# BAAAHS-BRN01-E.net
KiCad netlist of a schematic drawn in EAGLE
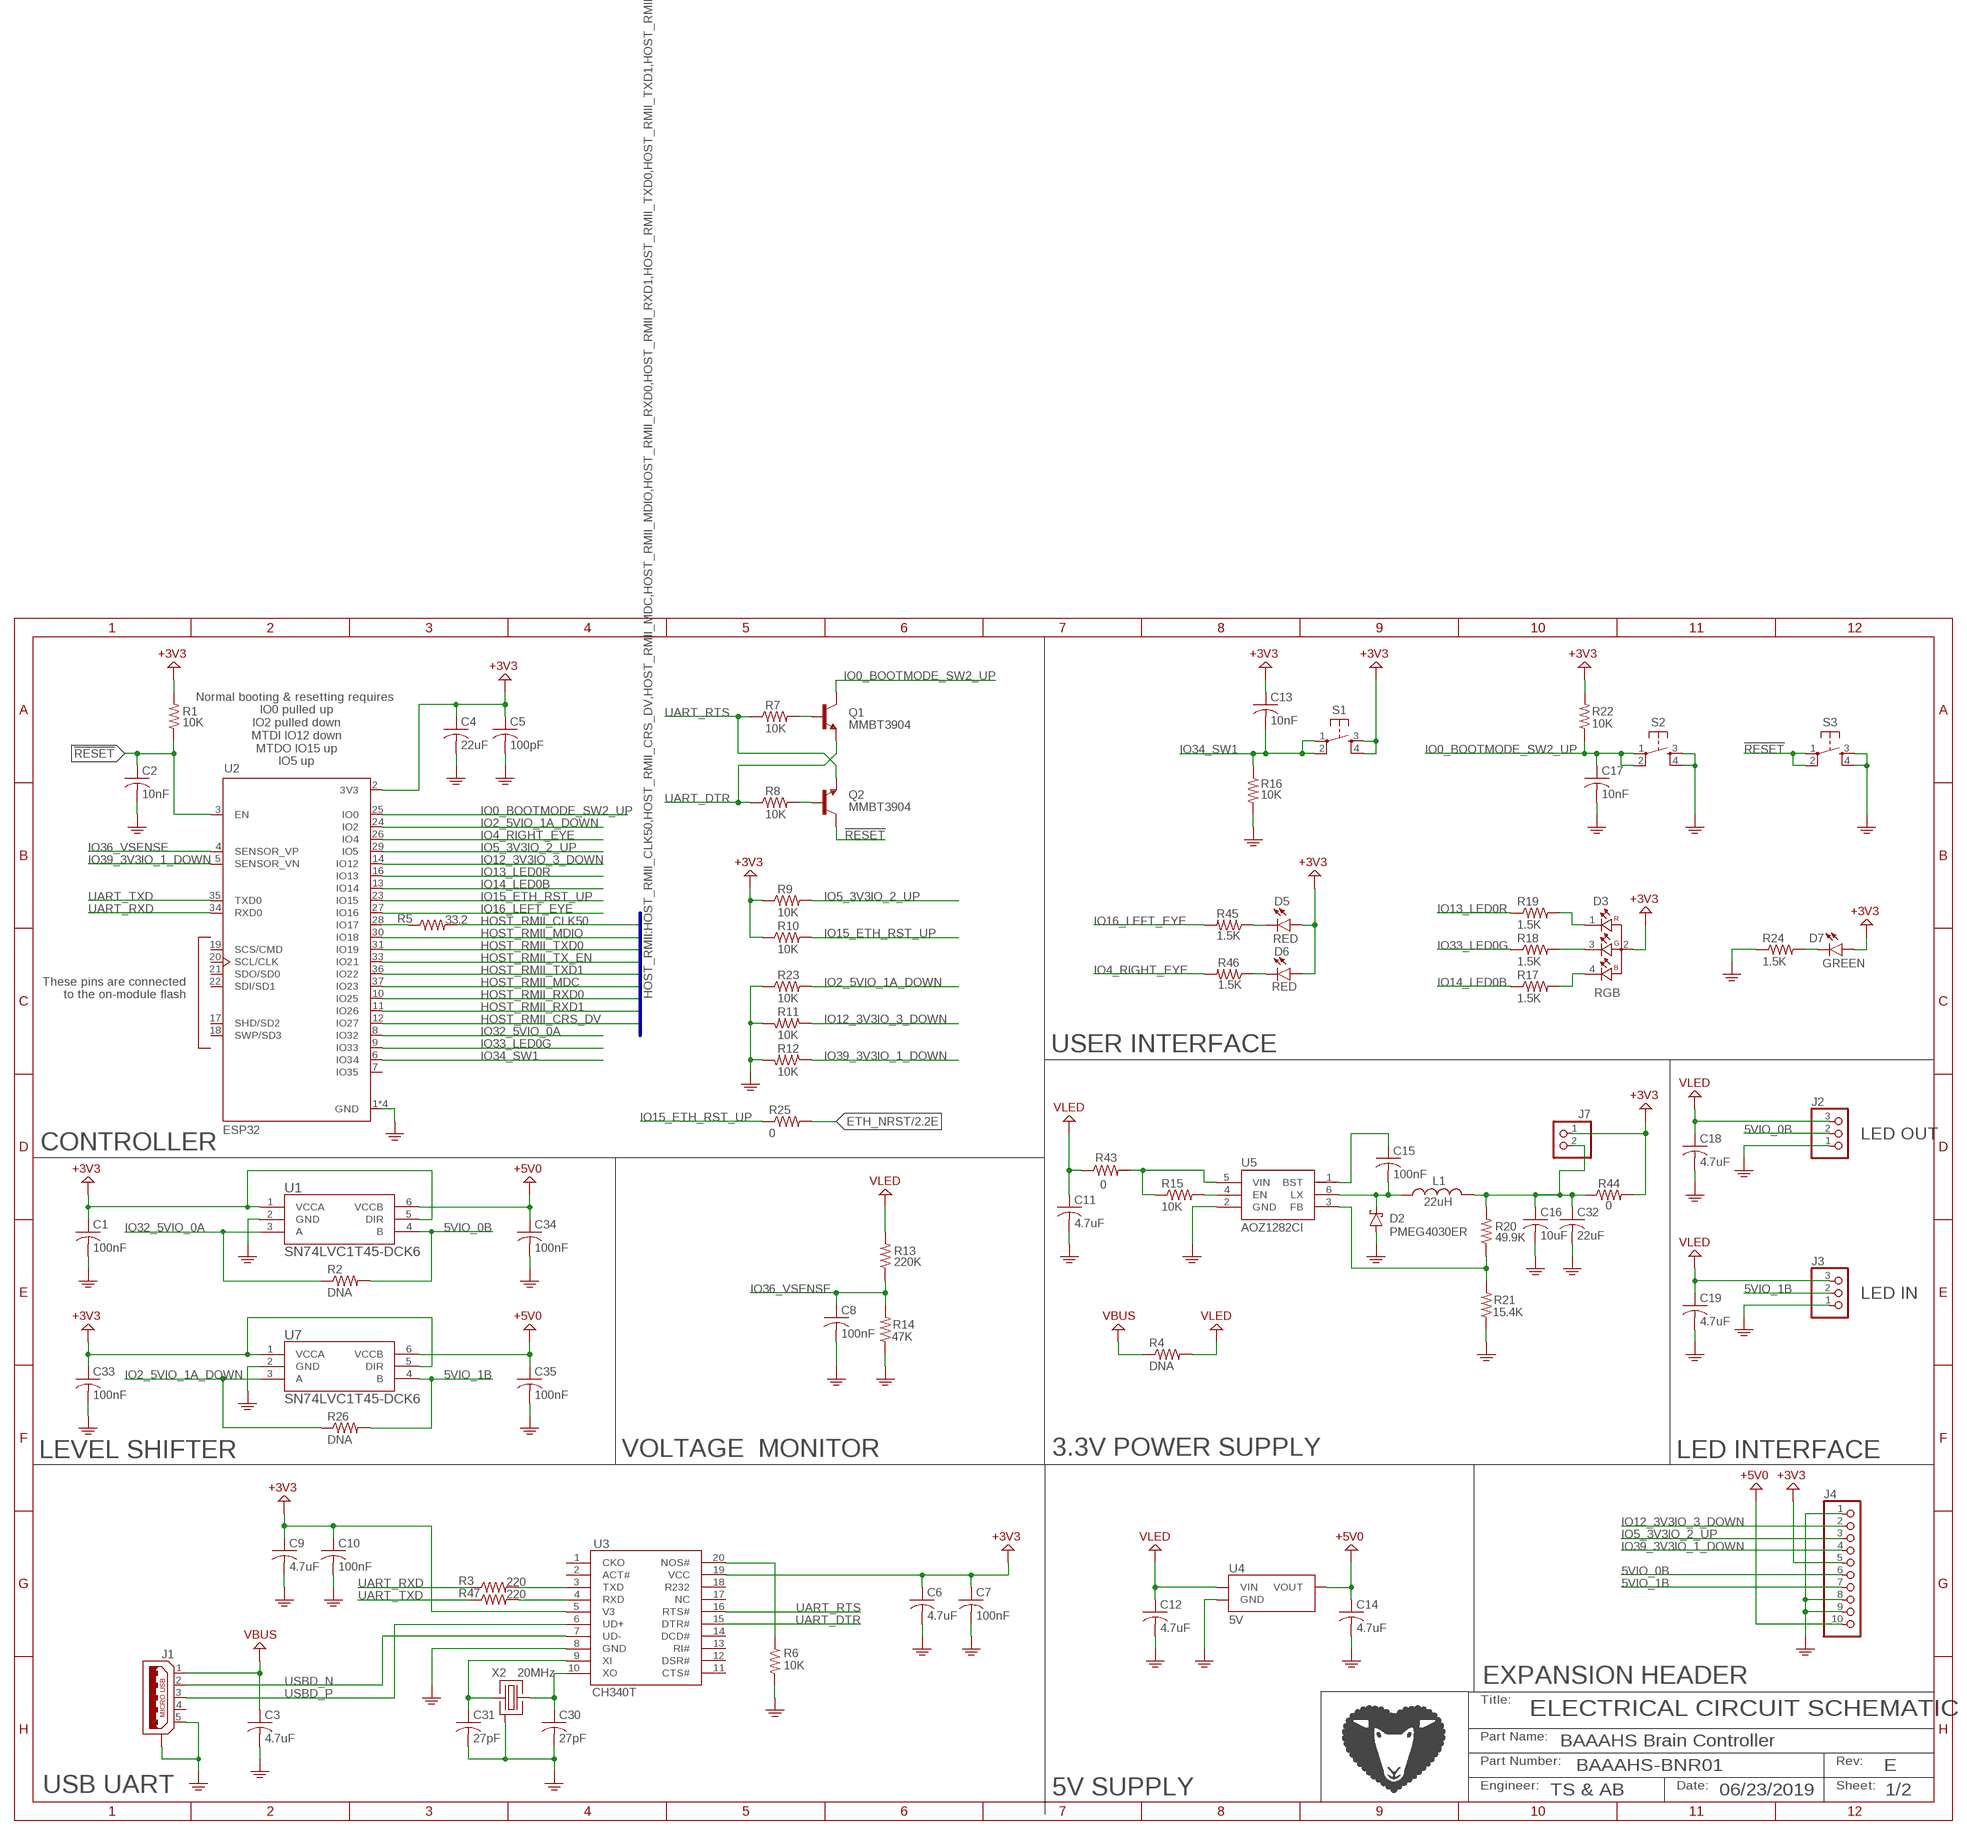
[diagram p0: schematic, sheet 1]
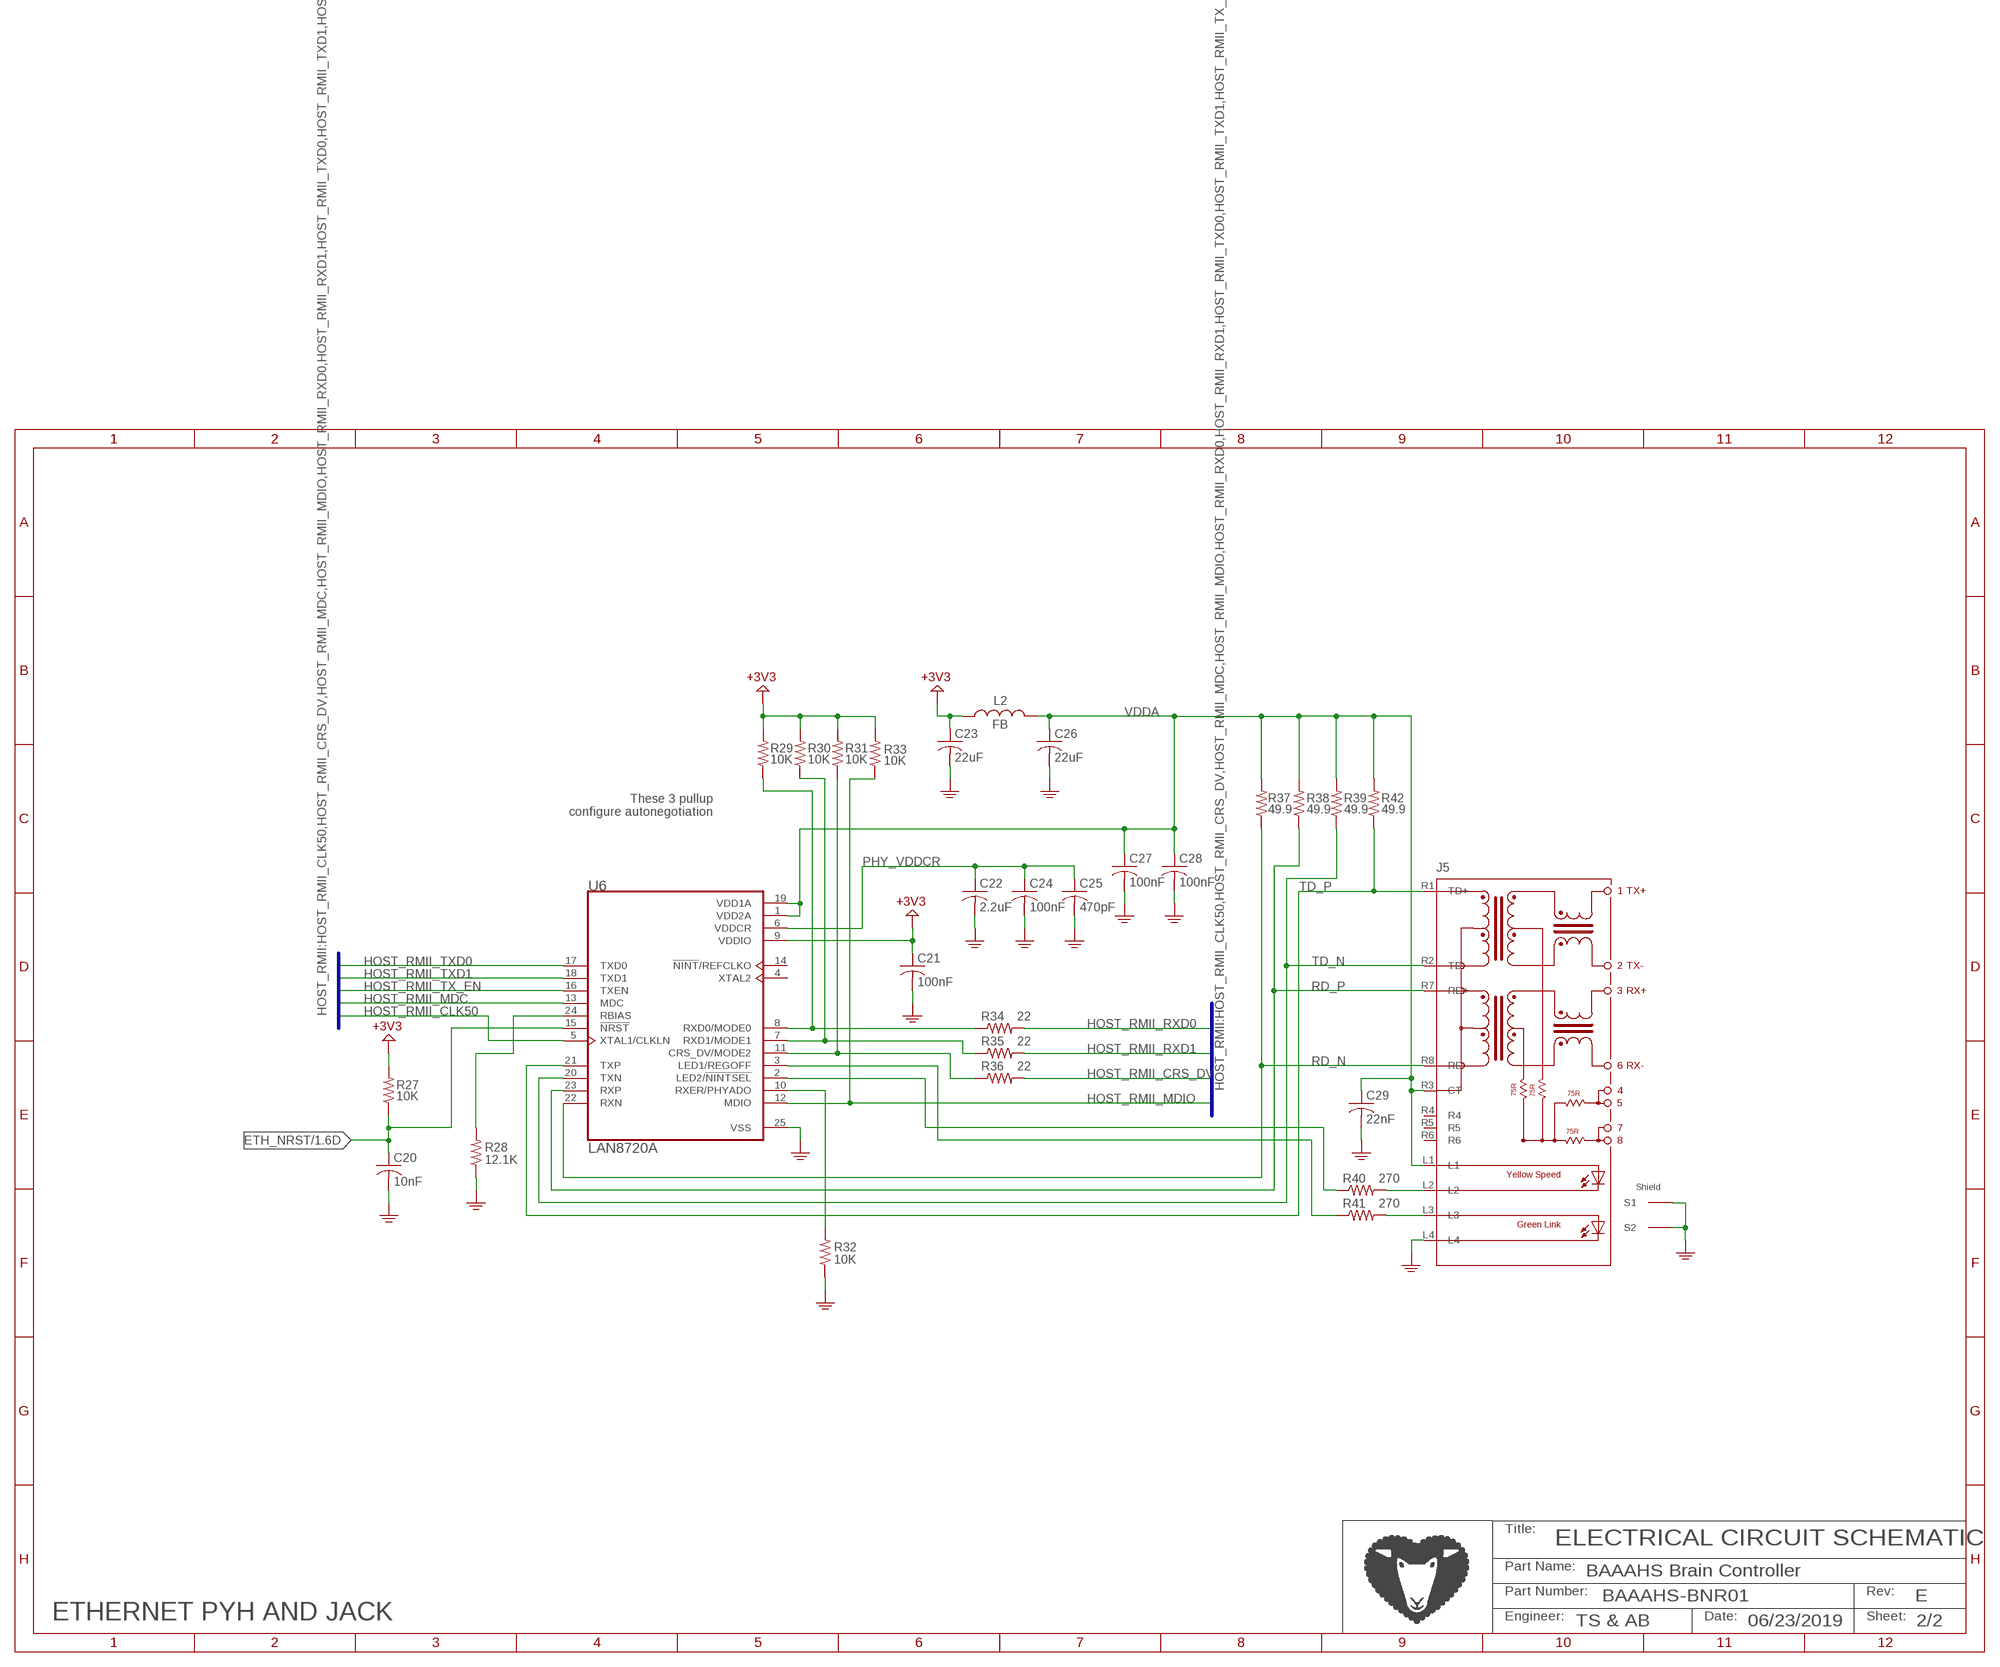
[diagram p1: schematic, sheet 2]

(export (version "E")
  (design (tool "Eeschema 10.0.6"))
  (components
    (comp (ref "C1")
      (value "100nF")
      (footprint "eagle-import:C0402")
      (fields (field (name "TOLERANCE") "+/-10%") (field (name "VOLTAGE") "25V"))
      (libsource (lib "eagle-import") (part "C-C0402-100NF_25V_10%"))
    )
    (comp (ref "C2")
      (value "10nF")
      (footprint "eagle-import:C0402")
      (fields (field (name "TOLERANCE") "+/-10%") (field (name "VOLTAGE") "16V"))
      (libsource (lib "eagle-import") (part "C-C0402-10NF_16V_10%"))
    )
    (comp (ref "C3")
      (value "4.7uF")
      (footprint "eagle-import:C0402")
      (fields (field (name "TOLERANCE") "+/-10%") (field (name "VOLTAGE") "10V"))
      (libsource (lib "eagle-import") (part "C-C0402-4.7UF_10V_10%"))
    )
    (comp (ref "C4")
      (value "22uF")
      (footprint "eagle-import:C0603")
      (fields (field (name "TOLERANCE") "+/-20%") (field (name "VOLTAGE") "10V"))
      (libsource (lib "eagle-import") (part "C-C0603-22UF_10V_20%"))
    )
    (comp (ref "C5")
      (value "100pF")
      (footprint "eagle-import:C0402")
      (fields (field (name "TOLERANCE") "+/-5%") (field (name "VOLTAGE") "50V"))
      (libsource (lib "eagle-import") (part "C-C0402-100PF_50V_5%"))
    )
    (comp (ref "C6")
      (value "4.7uF")
      (footprint "eagle-import:C0402")
      (fields (field (name "TOLERANCE") "+/-10%") (field (name "VOLTAGE") "10V"))
      (libsource (lib "eagle-import") (part "C-C0402-4.7UF_10V_10%"))
    )
    (comp (ref "C7")
      (value "100nF")
      (footprint "eagle-import:C0402")
      (fields (field (name "TOLERANCE") "+/-10%") (field (name "VOLTAGE") "25V"))
      (libsource (lib "eagle-import") (part "C-C0402-100NF_25V_10%"))
    )
    (comp (ref "C8")
      (value "100nF")
      (footprint "eagle-import:C0402")
      (fields (field (name "TOLERANCE") "+/-10%") (field (name "VOLTAGE") "25V"))
      (libsource (lib "eagle-import") (part "C-C0402-100NF_25V_10%"))
    )
    (comp (ref "C9")
      (value "4.7uF")
      (footprint "eagle-import:C0402")
      (fields (field (name "TOLERANCE") "+/-10%") (field (name "VOLTAGE") "10V"))
      (libsource (lib "eagle-import") (part "C-C0402-4.7UF_10V_10%"))
    )
    (comp (ref "C10")
      (value "100nF")
      (footprint "eagle-import:C0402")
      (fields (field (name "TOLERANCE") "+/-10%") (field (name "VOLTAGE") "25V"))
      (libsource (lib "eagle-import") (part "C-C0402-100NF_25V_10%"))
    )
    (comp (ref "C11")
      (value "4.7uF")
      (footprint "eagle-import:C0603")
      (fields (field (name "TOLERANCE") "+/-10%") (field (name "VOLTAGE") "25V"))
      (libsource (lib "eagle-import") (part "C-C0603-4.7UF_25V_10%"))
    )
    (comp (ref "C12")
      (value "4.7uF")
      (footprint "eagle-import:C0603")
      (fields (field (name "TOLERANCE") "+/-10%") (field (name "VOLTAGE") "25V"))
      (libsource (lib "eagle-import") (part "C-C0603-4.7UF_25V_10%"))
    )
    (comp (ref "C13")
      (value "10nF")
      (footprint "eagle-import:C0402")
      (fields (field (name "TOLERANCE") "+/-10%") (field (name "VOLTAGE") "16V"))
      (libsource (lib "eagle-import") (part "C-C0402-10NF_16V_10%"))
    )
    (comp (ref "C14")
      (value "4.7uF")
      (footprint "eagle-import:C0402")
      (fields (field (name "TOLERANCE") "+/-10%") (field (name "VOLTAGE") "10V"))
      (libsource (lib "eagle-import") (part "C-C0402-4.7UF_10V_10%"))
    )
    (comp (ref "C15")
      (value "100nF")
      (footprint "eagle-import:C0402")
      (fields (field (name "TOLERANCE") "+/-10%") (field (name "VOLTAGE") "25V"))
      (libsource (lib "eagle-import") (part "C-C0402-100NF_25V_10%"))
    )
    (comp (ref "C16")
      (value "10uF")
      (footprint "eagle-import:C0603")
      (fields (field (name "TOLERANCE") "+/-20%") (field (name "VOLTAGE") "25V"))
      (libsource (lib "eagle-import") (part "C-C0603-10UF_25V_20%"))
    )
    (comp (ref "C17")
      (value "10nF")
      (footprint "eagle-import:C0402")
      (fields (field (name "TOLERANCE") "+/-10%") (field (name "VOLTAGE") "16V"))
      (libsource (lib "eagle-import") (part "C-C0402-10NF_16V_10%"))
    )
    (comp (ref "C18")
      (value "4.7uF")
      (footprint "eagle-import:C0603")
      (fields (field (name "TOLERANCE") "+/-10%") (field (name "VOLTAGE") "25V"))
      (libsource (lib "eagle-import") (part "C-C0603-4.7UF_25V_10%"))
    )
    (comp (ref "C19")
      (value "4.7uF")
      (footprint "eagle-import:C0603")
      (fields (field (name "TOLERANCE") "+/-10%") (field (name "VOLTAGE") "25V"))
      (libsource (lib "eagle-import") (part "C-C0603-4.7UF_25V_10%"))
    )
    (comp (ref "C30")
      (value "27pF")
      (footprint "eagle-import:C0402")
      (fields (field (name "TOLERANCE") "+/-5%") (field (name "VOLTAGE") "50V"))
      (libsource (lib "eagle-import") (part "C-C0402-27PF_50V_5%"))
    )
    (comp (ref "C31")
      (value "27pF")
      (footprint "eagle-import:C0402")
      (fields (field (name "TOLERANCE") "+/-5%") (field (name "VOLTAGE") "50V"))
      (libsource (lib "eagle-import") (part "C-C0402-27PF_50V_5%"))
    )
    (comp (ref "C32")
      (value "22uF")
      (footprint "eagle-import:C0603")
      (fields (field (name "TOLERANCE") "+/-20%") (field (name "VOLTAGE") "10V"))
      (libsource (lib "eagle-import") (part "C-C0603-22UF_10V_20%"))
    )
    (comp (ref "C33")
      (value "100nF")
      (footprint "eagle-import:C0402")
      (fields (field (name "TOLERANCE") "+/-10%") (field (name "VOLTAGE") "25V"))
      (libsource (lib "eagle-import") (part "C-C0402-100NF_25V_10%"))
    )
    (comp (ref "C34")
      (value "100nF")
      (footprint "eagle-import:C0402")
      (fields (field (name "TOLERANCE") "+/-10%") (field (name "VOLTAGE") "25V"))
      (libsource (lib "eagle-import") (part "C-C0402-100NF_25V_10%"))
    )
    (comp (ref "C35")
      (value "100nF")
      (footprint "eagle-import:C0402")
      (fields (field (name "TOLERANCE") "+/-10%") (field (name "VOLTAGE") "25V"))
      (libsource (lib "eagle-import") (part "C-C0402-100NF_25V_10%"))
    )
    (comp (ref "D2")
      (value "PMEG4030ER")
      (footprint "eagle-import:SOD123")
      (libsource (lib "eagle-import") (part "D_SCHOTTKY-SOD123-PMEG4030ER_40V"))
    )
    (comp (ref "D3")
      (value "RGB")
      (footprint "eagle-import:RGB1616")
      (libsource (lib "eagle-import") (part "RGB_LED-RGB1616"))
    )
    (comp (ref "D5")
      (value "RED")
      (footprint "eagle-import:D0603")
      (libsource (lib "eagle-import") (part "LED-D0603-RED_54MCD"))
    )
    (comp (ref "D6")
      (value "RED")
      (footprint "eagle-import:D0603")
      (libsource (lib "eagle-import") (part "LED-D0603-RED_54MCD"))
    )
    (comp (ref "D7")
      (value "GREEN")
      (footprint "eagle-import:D0603")
      (libsource (lib "eagle-import") (part "LED-D0603-GREEN_35MCD"))
    )
    (comp (ref "J1")
      (value "USB_MICRO-FCI-USB_MICRO_A_RA")
      (footprint "eagle-import:USB_MICRO_A_RA")
      (libsource (lib "eagle-import") (part "USB_MICRO-USB_MICRO_A_RA-FCI"))
    )
    (comp (ref "J2")
      (value "PINHD1X3-20AWG")
      (footprint "eagle-import:3WAY_LED_WIRES")
      (libsource (lib "eagle-import") (part "PINHD1X3-20AWG"))
    )
    (comp (ref "J3")
      (value "PINHD1X3-20AWG")
      (footprint "eagle-import:3WAY_LED_WIRES")
      (libsource (lib "eagle-import") (part "PINHD1X3-20AWG"))
    )
    (comp (ref "J4")
      (value "PINHD1X10-1X10")
      (footprint "eagle-import:1X10")
      (libsource (lib "eagle-import") (part "PINHD1X10-1X10"))
    )
    (comp (ref "J7")
      (value "PINHD1X2-1X02")
      (footprint "eagle-import:1X02")
      (libsource (lib "eagle-import") (part "PINHD1X2-1X02"))
    )
    (comp (ref "L1")
      (value "22uH")
      (footprint "eagle-import:NRG4026")
      (libsource (lib "eagle-import") (part "L-NRG4026-22UH__290MOHM_700MA"))
    )
    (comp (ref "Q1")
      (value "MMBT3904")
      (footprint "eagle-import:SOT23")
      (fields (field (name "VOLTAGE") "40V"))
      (libsource (lib "eagle-import") (part "NPN-SOT23-MMBT3904_40V"))
    )
    (comp (ref "Q2")
      (value "MMBT3904")
      (footprint "eagle-import:SOT23")
      (fields (field (name "VOLTAGE") "40V"))
      (libsource (lib "eagle-import") (part "NPN-SOT23-MMBT3904_40V"))
    )
    (comp (ref "R1")
      (value "10K")
      (footprint "eagle-import:R0402")
      (fields (field (name "POWER") "1/16W") (field (name "TOLERANCE") "1%"))
      (libsource (lib "eagle-import") (part "R-R0402-10K_1%"))
    )
    (comp (ref "R2")
      (value "DNA")
      (footprint "eagle-import:R0402")
      (libsource (lib "eagle-import") (part "R-R0402-DNA"))
    )
    (comp (ref "R3")
      (value "220")
      (footprint "eagle-import:R0402")
      (fields (field (name "POWER") "1/16W") (field (name "TOLERANCE") "1%"))
      (libsource (lib "eagle-import") (part "R-R0402-220_1%"))
    )
    (comp (ref "R4")
      (value "DNA")
      (footprint "eagle-import:R0603")
      (fields (field (name "POWER") "1/16W"))
      (libsource (lib "eagle-import") (part "R-R0603-DNA"))
    )
    (comp (ref "R5")
      (value "33.2")
      (footprint "eagle-import:R0402")
      (fields (field (name "POWER") "1/16W") (field (name "TOLERANCE") "1%"))
      (libsource (lib "eagle-import") (part "R-R0402-33.2_1%"))
    )
    (comp (ref "R6")
      (value "10K")
      (footprint "eagle-import:R0402")
      (fields (field (name "POWER") "1/16W") (field (name "TOLERANCE") "1%"))
      (libsource (lib "eagle-import") (part "R-R0402-10K_1%"))
    )
    (comp (ref "R7")
      (value "10K")
      (footprint "eagle-import:R0402")
      (fields (field (name "POWER") "1/16W") (field (name "TOLERANCE") "1%"))
      (libsource (lib "eagle-import") (part "R-R0402-10K_1%"))
    )
    (comp (ref "R8")
      (value "10K")
      (footprint "eagle-import:R0402")
      (fields (field (name "POWER") "1/16W") (field (name "TOLERANCE") "1%"))
      (libsource (lib "eagle-import") (part "R-R0402-10K_1%"))
    )
    (comp (ref "R9")
      (value "10K")
      (footprint "eagle-import:R0402")
      (fields (field (name "POWER") "1/16W") (field (name "TOLERANCE") "1%"))
      (libsource (lib "eagle-import") (part "R-R0402-10K_1%"))
    )
    (comp (ref "R10")
      (value "10K")
      (footprint "eagle-import:R0402")
      (fields (field (name "POWER") "1/16W") (field (name "TOLERANCE") "1%"))
      (libsource (lib "eagle-import") (part "R-R0402-10K_1%"))
    )
    (comp (ref "R11")
      (value "10K")
      (footprint "eagle-import:R0402")
      (fields (field (name "POWER") "1/16W") (field (name "TOLERANCE") "1%"))
      (libsource (lib "eagle-import") (part "R-R0402-10K_1%"))
    )
    (comp (ref "R12")
      (value "10K")
      (footprint "eagle-import:R0402")
      (fields (field (name "POWER") "1/16W") (field (name "TOLERANCE") "1%"))
      (libsource (lib "eagle-import") (part "R-R0402-10K_1%"))
    )
    (comp (ref "R13")
      (value "220K")
      (footprint "eagle-import:R0402")
      (fields (field (name "POWER") "1/16W") (field (name "TOLERANCE") "1%"))
      (libsource (lib "eagle-import") (part "R-R0402-220K_1%"))
    )
    (comp (ref "R14")
      (value "47K")
      (footprint "eagle-import:R0402")
      (fields (field (name "POWER") "1/16W") (field (name "TOLERANCE") "1%"))
      (libsource (lib "eagle-import") (part "R-R0402-47K_1%"))
    )
    (comp (ref "R15")
      (value "10K")
      (footprint "eagle-import:R0402")
      (fields (field (name "POWER") "1/16W") (field (name "TOLERANCE") "1%"))
      (libsource (lib "eagle-import") (part "R-R0402-10K_1%"))
    )
    (comp (ref "R16")
      (value "10K")
      (footprint "eagle-import:R0402")
      (fields (field (name "POWER") "1/16W") (field (name "TOLERANCE") "1%"))
      (libsource (lib "eagle-import") (part "R-R0402-10K_1%"))
    )
    (comp (ref "R17")
      (value "1.5K")
      (footprint "eagle-import:R0402")
      (fields (field (name "POWER") "1/16W") (field (name "TOLERANCE") "1%"))
      (libsource (lib "eagle-import") (part "R-R0402-1.5K_1%"))
    )
    (comp (ref "R18")
      (value "1.5K")
      (footprint "eagle-import:R0402")
      (fields (field (name "POWER") "1/16W") (field (name "TOLERANCE") "1%"))
      (libsource (lib "eagle-import") (part "R-R0402-1.5K_1%"))
    )
    (comp (ref "R19")
      (value "1.5K")
      (footprint "eagle-import:R0402")
      (fields (field (name "POWER") "1/16W") (field (name "TOLERANCE") "1%"))
      (libsource (lib "eagle-import") (part "R-R0402-1.5K_1%"))
    )
    (comp (ref "R20")
      (value "49.9K")
      (footprint "eagle-import:R0402")
      (fields (field (name "POWER") "1/16W") (field (name "TOLERANCE") "1%"))
      (libsource (lib "eagle-import") (part "R-R0402-49.9K_1%"))
    )
    (comp (ref "R21")
      (value "15.4K")
      (footprint "eagle-import:R0402")
      (fields (field (name "POWER") "1/16W") (field (name "TOLERANCE") "1%"))
      (libsource (lib "eagle-import") (part "R-R0402-15.4K_1%"))
    )
    (comp (ref "R22")
      (value "10K")
      (footprint "eagle-import:R0402")
      (fields (field (name "POWER") "1/16W") (field (name "TOLERANCE") "1%"))
      (libsource (lib "eagle-import") (part "R-R0402-10K_1%"))
    )
    (comp (ref "R23")
      (value "10K")
      (footprint "eagle-import:R0402")
      (fields (field (name "POWER") "1/16W") (field (name "TOLERANCE") "1%"))
      (libsource (lib "eagle-import") (part "R-R0402-10K_1%"))
    )
    (comp (ref "R24")
      (value "1.5K")
      (footprint "eagle-import:R0402")
      (fields (field (name "POWER") "1/16W") (field (name "TOLERANCE") "1%"))
      (libsource (lib "eagle-import") (part "R-R0402-1.5K_1%"))
    )
    (comp (ref "R25")
      (value "0")
      (footprint "eagle-import:R0402")
      (fields (field (name "POWER") "1/16W") (field (name "TOLERANCE") "1%"))
      (libsource (lib "eagle-import") (part "R-R0402-0_1%"))
    )
    (comp (ref "R26")
      (value "DNA")
      (footprint "eagle-import:R0402")
      (libsource (lib "eagle-import") (part "R-R0402-DNA"))
    )
    (comp (ref "R43")
      (value "0")
      (footprint "eagle-import:R0603")
      (fields (field (name "POWER") "1/10W") (field (name "TOLERANCE") "1%"))
      (libsource (lib "eagle-import") (part "R-R0603-0_1%"))
    )
    (comp (ref "R44")
      (value "0")
      (footprint "eagle-import:R0603")
      (fields (field (name "POWER") "1/10W") (field (name "TOLERANCE") "1%"))
      (libsource (lib "eagle-import") (part "R-R0603-0_1%"))
    )
    (comp (ref "R45")
      (value "1.5K")
      (footprint "eagle-import:R0402")
      (fields (field (name "POWER") "1/16W") (field (name "TOLERANCE") "1%"))
      (libsource (lib "eagle-import") (part "R-R0402-1.5K_1%"))
    )
    (comp (ref "R46")
      (value "1.5K")
      (footprint "eagle-import:R0402")
      (fields (field (name "POWER") "1/16W") (field (name "TOLERANCE") "1%"))
      (libsource (lib "eagle-import") (part "R-R0402-1.5K_1%"))
    )
    (comp (ref "R47")
      (value "220")
      (footprint "eagle-import:R0402")
      (fields (field (name "POWER") "1/16W") (field (name "TOLERANCE") "1%"))
      (libsource (lib "eagle-import") (part "R-R0402-220_1%"))
    )
    (comp (ref "S1")
      (value "SW4-SM6MM")
      (footprint "eagle-import:SM6MM")
      (libsource (lib "eagle-import") (part "SW4-SM6MM"))
    )
    (comp (ref "S2")
      (value "SW4-SM6MM")
      (footprint "eagle-import:SM6MM")
      (libsource (lib "eagle-import") (part "SW4-SM6MM"))
    )
    (comp (ref "S3")
      (value "SW4-SM6MM")
      (footprint "eagle-import:SM6MM")
      (libsource (lib "eagle-import") (part "SW4-SM6MM"))
    )
    (comp (ref "U1")
      (value "SN74LVC1T45-DCK6")
      (footprint "eagle-import:DCK6")
      (libsource (lib "eagle-import") (part "SN74LVC1T45-DCK6"))
    )
    (comp (ref "U2")
      (value "ESP32")
      (footprint "eagle-import:MODULE_ESP32WROOM32D")
      (libsource (lib "eagle-import") (part "ESP32WROOM32D-MODULE_ESP32WROOM32D"))
    )
    (comp (ref "U3")
      (value "CH340T")
      (footprint "eagle-import:SSOP20")
      (libsource (lib "eagle-import") (part "CH340T-SSOP20"))
    )
    (comp (ref "U4")
      (value "5V")
      (footprint "eagle-import:SOT23")
      (libsource (lib "eagle-import") (part "SE8550X2-SOT23"))
    )
    (comp (ref "U5")
      (value "AOZ1282CI")
      (footprint "eagle-import:SOT23_6")
      (libsource (lib "eagle-import") (part "AOZ1282CI-SOT23_6"))
    )
    (comp (ref "U7")
      (value "SN74LVC1T45-DCK6")
      (footprint "eagle-import:DCK6")
      (libsource (lib "eagle-import") (part "SN74LVC1T45-DCK6"))
    )
    (comp (ref "X2")
      (value "20MHz")
      (footprint "eagle-import:3.2X2.5_4P")
      (libsource (lib "eagle-import") (part "XTAL33.2X2.5_4P-20MHZ_20PF_30PPM"))
    )
    (comp (ref "C20")
      (value "10nF")
      (footprint "eagle-import:C0402")
      (fields (field (name "TOLERANCE") "+/-10%") (field (name "VOLTAGE") "16V"))
      (libsource (lib "eagle-import") (part "C-C0402-10NF_16V_10%"))
    )
    (comp (ref "C21")
      (value "100nF")
      (footprint "eagle-import:C0402")
      (fields (field (name "TOLERANCE") "+/-10%") (field (name "VOLTAGE") "25V"))
      (libsource (lib "eagle-import") (part "C-C0402-100NF_25V_10%"))
    )
    (comp (ref "C22")
      (value "2.2uF")
      (footprint "eagle-import:C0603")
      (fields (field (name "TOLERANCE") "+/-10%") (field (name "VOLTAGE") "16V"))
      (libsource (lib "eagle-import") (part "C-C0603-2.2UF_16V_10%"))
    )
    (comp (ref "C23")
      (value "22uF")
      (footprint "eagle-import:C0603")
      (fields (field (name "TOLERANCE") "+/-20%") (field (name "VOLTAGE") "10V"))
      (libsource (lib "eagle-import") (part "C-C0603-22UF_10V_20%"))
    )
    (comp (ref "C24")
      (value "100nF")
      (footprint "eagle-import:C0402")
      (fields (field (name "TOLERANCE") "+/-10%") (field (name "VOLTAGE") "25V"))
      (libsource (lib "eagle-import") (part "C-C0402-100NF_25V_10%"))
    )
    (comp (ref "C25")
      (value "470pF")
      (footprint "eagle-import:C0402")
      (fields (field (name "TOLERANCE") "+/-10%") (field (name "VOLTAGE") "50V"))
      (libsource (lib "eagle-import") (part "C-C0402-470PF_50V_10%"))
    )
    (comp (ref "C26")
      (value "22uF")
      (footprint "eagle-import:C0603")
      (fields (field (name "TOLERANCE") "+/-20%") (field (name "VOLTAGE") "10V"))
      (libsource (lib "eagle-import") (part "C-C0603-22UF_10V_20%"))
    )
    (comp (ref "C27")
      (value "100nF")
      (footprint "eagle-import:C0402")
      (fields (field (name "TOLERANCE") "+/-10%") (field (name "VOLTAGE") "25V"))
      (libsource (lib "eagle-import") (part "C-C0402-100NF_25V_10%"))
    )
    (comp (ref "C28")
      (value "100nF")
      (footprint "eagle-import:C0402")
      (fields (field (name "TOLERANCE") "+/-10%") (field (name "VOLTAGE") "25V"))
      (libsource (lib "eagle-import") (part "C-C0402-100NF_25V_10%"))
    )
    (comp (ref "C29")
      (value "22nF")
      (footprint "eagle-import:C0402")
      (fields (field (name "TOLERANCE") "+/-10%") (field (name "VOLTAGE") "16V"))
      (libsource (lib "eagle-import") (part "C-C0402-22NF_16V_10%"))
    )
    (comp (ref "J5")
      (value "RB1-125BAG1A")
      (footprint "eagle-import:WIZNET_RB1-125BAG1A")
      (libsource (lib "eagle-import") (part "RB1-125BAG1A"))
    )
    (comp (ref "L2")
      (value "FB")
      (footprint "eagle-import:L0603")
      (libsource (lib "eagle-import") (part "FB-L0603-0.45OHM_470OHM_200MA"))
    )
    (comp (ref "R27")
      (value "10K")
      (footprint "eagle-import:R0402")
      (fields (field (name "POWER") "1/16W") (field (name "TOLERANCE") "1%"))
      (libsource (lib "eagle-import") (part "R-R0402-10K_1%"))
    )
    (comp (ref "R28")
      (value "12.1K")
      (footprint "eagle-import:R0402")
      (fields (field (name "POWER") "1/16W") (field (name "TOLERANCE") "1%"))
      (libsource (lib "eagle-import") (part "R-R0402-12.1K_1%"))
    )
    (comp (ref "R29")
      (value "10K")
      (footprint "eagle-import:R0402")
      (fields (field (name "POWER") "1/16W") (field (name "TOLERANCE") "1%"))
      (libsource (lib "eagle-import") (part "R-R0402-10K_1%"))
    )
    (comp (ref "R30")
      (value "10K")
      (footprint "eagle-import:R0402")
      (fields (field (name "POWER") "1/16W") (field (name "TOLERANCE") "1%"))
      (libsource (lib "eagle-import") (part "R-R0402-10K_1%"))
    )
    (comp (ref "R31")
      (value "10K")
      (footprint "eagle-import:R0402")
      (fields (field (name "POWER") "1/16W") (field (name "TOLERANCE") "1%"))
      (libsource (lib "eagle-import") (part "R-R0402-10K_1%"))
    )
    (comp (ref "R32")
      (value "10K")
      (footprint "eagle-import:R0402")
      (fields (field (name "POWER") "1/16W") (field (name "TOLERANCE") "1%"))
      (libsource (lib "eagle-import") (part "R-R0402-10K_1%"))
    )
    (comp (ref "R33")
      (value "10K")
      (footprint "eagle-import:R0402")
      (fields (field (name "POWER") "1/16W") (field (name "TOLERANCE") "1%"))
      (libsource (lib "eagle-import") (part "R-R0402-10K_1%"))
    )
    (comp (ref "R34")
      (value "22")
      (footprint "eagle-import:R0402")
      (fields (field (name "POWER") "1/16W") (field (name "TOLERANCE") "1%"))
      (libsource (lib "eagle-import") (part "R-R0402-22_1%"))
    )
    (comp (ref "R35")
      (value "22")
      (footprint "eagle-import:R0402")
      (fields (field (name "POWER") "1/16W") (field (name "TOLERANCE") "1%"))
      (libsource (lib "eagle-import") (part "R-R0402-22_1%"))
    )
    (comp (ref "R36")
      (value "22")
      (footprint "eagle-import:R0402")
      (fields (field (name "POWER") "1/16W") (field (name "TOLERANCE") "1%"))
      (libsource (lib "eagle-import") (part "R-R0402-22_1%"))
    )
    (comp (ref "R37")
      (value "49.9")
      (footprint "eagle-import:R0402")
      (fields (field (name "POWER") "1/16W") (field (name "TOLERANCE") "1%"))
      (libsource (lib "eagle-import") (part "R-R0402-49.9_1%"))
    )
    (comp (ref "R38")
      (value "49.9")
      (footprint "eagle-import:R0402")
      (fields (field (name "POWER") "1/16W") (field (name "TOLERANCE") "1%"))
      (libsource (lib "eagle-import") (part "R-R0402-49.9_1%"))
    )
    (comp (ref "R39")
      (value "49.9")
      (footprint "eagle-import:R0402")
      (fields (field (name "POWER") "1/16W") (field (name "TOLERANCE") "1%"))
      (libsource (lib "eagle-import") (part "R-R0402-49.9_1%"))
    )
    (comp (ref "R40")
      (value "270")
      (footprint "eagle-import:R0402")
      (fields (field (name "POWER") "1/16W") (field (name "TOLERANCE") "1%"))
      (libsource (lib "eagle-import") (part "R-R0402-270_1%"))
    )
    (comp (ref "R41")
      (value "270")
      (footprint "eagle-import:R0402")
      (fields (field (name "POWER") "1/16W") (field (name "TOLERANCE") "1%"))
      (libsource (lib "eagle-import") (part "R-R0402-270_1%"))
    )
    (comp (ref "R42")
      (value "49.9")
      (footprint "eagle-import:R0402")
      (fields (field (name "POWER") "1/16W") (field (name "TOLERANCE") "1%"))
      (libsource (lib "eagle-import") (part "R-R0402-49.9_1%"))
    )
    (comp (ref "U6")
      (value "LAN8720A")
      (footprint "eagle-import:QFN50P400X400X100-25N")
      (libsource (lib "eagle-import") (part "LAN8720A-CP"))
    )
  )
  (nets
    (net (code "5") (name "3V3") (class "Default")
      (node (ref "C1") (pin "1") (pinfunction "1_1") (pintype "passive"))
      (node (ref "C10") (pin "1") (pinfunction "1_1") (pintype "passive"))
      (node (ref "C13") (pin "1") (pinfunction "1_1") (pintype "passive"))
      (node (ref "C21") (pin "1") (pinfunction "1_1") (pintype "passive"))
      (node (ref "C23") (pin "1") (pinfunction "1_1") (pintype "passive"))
      (node (ref "C33") (pin "1") (pinfunction "1_1") (pintype "passive"))
      (node (ref "C4") (pin "1") (pinfunction "1_1") (pintype "passive"))
      (node (ref "C5") (pin "1") (pinfunction "1_1") (pintype "passive"))
      (node (ref "C6") (pin "1") (pinfunction "1_1") (pintype "passive"))
      (node (ref "C7") (pin "1") (pinfunction "1_1") (pintype "passive"))
      (node (ref "C9") (pin "1") (pinfunction "1_1") (pintype "passive"))
      (node (ref "D3") (pin "2") (pinfunction "CA_2") (pintype "passive"))
      (node (ref "D5") (pin "A") (pinfunction "A_A") (pintype "passive"))
      (node (ref "D6") (pin "A") (pinfunction "A_A") (pintype "passive"))
      (node (ref "D7") (pin "A") (pinfunction "A_A") (pintype "passive"))
      (node (ref "J4") (pin "5") (pinfunction "5_5") (pintype "passive"))
      (node (ref "J7") (pin "1") (pinfunction "1_1") (pintype "passive"))
      (node (ref "L2") (pin "1") (pinfunction "1_1") (pintype "passive"))
      (node (ref "R1") (pin "2") (pinfunction "2_2") (pintype "passive"))
      (node (ref "R10") (pin "1") (pinfunction "1_1") (pintype "passive"))
      (node (ref "R22") (pin "2") (pinfunction "2_2") (pintype "passive"))
      (node (ref "R27") (pin "2") (pinfunction "2_2") (pintype "passive"))
      (node (ref "R29") (pin "2") (pinfunction "2_2") (pintype "passive"))
      (node (ref "R30") (pin "2") (pinfunction "2_2") (pintype "passive"))
      (node (ref "R31") (pin "2") (pinfunction "2_2") (pintype "passive"))
      (node (ref "R33") (pin "2") (pinfunction "2_2") (pintype "passive"))
      (node (ref "R44") (pin "2") (pinfunction "2_2") (pintype "passive"))
      (node (ref "R9") (pin "1") (pinfunction "1_1") (pintype "passive"))
      (node (ref "S1") (pin "3") (pinfunction "S_3") (pintype "passive"))
      (node (ref "S1") (pin "4") (pinfunction "S1_4") (pintype "passive"))
      (node (ref "U1") (pin "1") (pinfunction "VCCA_1") (pintype "power_in"))
      (node (ref "U1") (pin "5") (pinfunction "DIR_5") (pintype "input"))
      (node (ref "U2") (pin "2") (pinfunction "3V3_2") (pintype "power_in"))
      (node (ref "U3") (pin "19") (pinfunction "VCC_19") (pintype "power_in"))
      (node (ref "U3") (pin "5") (pinfunction "V3_5") (pintype "power_in"))
      (node (ref "U6") (pin "9") (pinfunction "VDDIO_9") (pintype "power_in"))
      (node (ref "U7") (pin "1") (pinfunction "VCCA_1") (pintype "power_in"))
      (node (ref "U7") (pin "5") (pinfunction "DIR_5") (pintype "input"))
    )
    (net (code "6") (name "5V0") (class "Default")
      (node (ref "C14") (pin "1") (pinfunction "1_1") (pintype "passive"))
      (node (ref "C34") (pin "1") (pinfunction "1_1") (pintype "passive"))
      (node (ref "C35") (pin "1") (pinfunction "1_1") (pintype "passive"))
      (node (ref "J4") (pin "10") (pinfunction "10_10") (pintype "passive"))
      (node (ref "U1") (pin "6") (pinfunction "VCCB_6") (pintype "power_in"))
      (node (ref "U4") (pin "2") (pinfunction "VOUT_2") (pintype "bidirectional"))
      (node (ref "U7") (pin "6") (pinfunction "VCCB_6") (pintype "power_in"))
    )
    (net (code "7") (name "5VIO_0B") (class "Default")
      (node (ref "J2") (pin "2") (pinfunction "2_2") (pintype "passive"))
      (node (ref "J4") (pin "6") (pinfunction "6_6") (pintype "passive"))
      (node (ref "R2") (pin "2") (pinfunction "2_2") (pintype "passive"))
      (node (ref "U1") (pin "4") (pinfunction "B_4") (pintype "input"))
    )
    (net (code "8") (name "5VIO_1B") (class "Default")
      (node (ref "J3") (pin "2") (pinfunction "2_2") (pintype "passive"))
      (node (ref "J4") (pin "7") (pinfunction "7_7") (pintype "passive"))
      (node (ref "R26") (pin "2") (pinfunction "2_2") (pintype "passive"))
      (node (ref "U7") (pin "4") (pinfunction "B_4") (pintype "input"))
    )
    (net (code "9") (name "ETH_NRST") (class "Default")
      (node (ref "C20") (pin "1") (pinfunction "1_1") (pintype "passive"))
      (node (ref "R25") (pin "2") (pinfunction "2_2") (pintype "passive"))
      (node (ref "R27") (pin "1") (pinfunction "1_1") (pintype "passive"))
      (node (ref "U6") (pin "15") (pinfunction "~{NRST}_15") (pintype "input"))
    )
    (net (code "10") (name "GND") (class "Default")
      (node (ref "C1") (pin "2") (pinfunction "2_2") (pintype "passive"))
      (node (ref "C10") (pin "2") (pinfunction "2_2") (pintype "passive"))
      (node (ref "C11") (pin "2") (pinfunction "2_2") (pintype "passive"))
      (node (ref "C12") (pin "2") (pinfunction "2_2") (pintype "passive"))
      (node (ref "C14") (pin "2") (pinfunction "2_2") (pintype "passive"))
      (node (ref "C16") (pin "2") (pinfunction "2_2") (pintype "passive"))
      (node (ref "C17") (pin "2") (pinfunction "2_2") (pintype "passive"))
      (node (ref "C18") (pin "2") (pinfunction "2_2") (pintype "passive"))
      (node (ref "C19") (pin "2") (pinfunction "2_2") (pintype "passive"))
      (node (ref "C2") (pin "2") (pinfunction "2_2") (pintype "passive"))
      (node (ref "C20") (pin "2") (pinfunction "2_2") (pintype "passive"))
      (node (ref "C21") (pin "2") (pinfunction "2_2") (pintype "passive"))
      (node (ref "C22") (pin "2") (pinfunction "2_2") (pintype "passive"))
      (node (ref "C23") (pin "2") (pinfunction "2_2") (pintype "passive"))
      (node (ref "C24") (pin "2") (pinfunction "2_2") (pintype "passive"))
      (node (ref "C25") (pin "2") (pinfunction "2_2") (pintype "passive"))
      (node (ref "C26") (pin "2") (pinfunction "2_2") (pintype "passive"))
      (node (ref "C27") (pin "2") (pinfunction "2_2") (pintype "passive"))
      (node (ref "C28") (pin "2") (pinfunction "2_2") (pintype "passive"))
      (node (ref "C29") (pin "2") (pinfunction "2_2") (pintype "passive"))
      (node (ref "C3") (pin "2") (pinfunction "2_2") (pintype "passive"))
      (node (ref "C30") (pin "2") (pinfunction "2_2") (pintype "passive"))
      (node (ref "C31") (pin "2") (pinfunction "2_2") (pintype "passive"))
      (node (ref "C32") (pin "2") (pinfunction "2_2") (pintype "passive"))
      (node (ref "C33") (pin "2") (pinfunction "2_2") (pintype "passive"))
      (node (ref "C34") (pin "2") (pinfunction "2_2") (pintype "passive"))
      (node (ref "C35") (pin "2") (pinfunction "2_2") (pintype "passive"))
      (node (ref "C4") (pin "2") (pinfunction "2_2") (pintype "passive"))
      (node (ref "C5") (pin "2") (pinfunction "2_2") (pintype "passive"))
      (node (ref "C6") (pin "2") (pinfunction "2_2") (pintype "passive"))
      (node (ref "C7") (pin "2") (pinfunction "2_2") (pintype "passive"))
      (node (ref "C8") (pin "2") (pinfunction "2_2") (pintype "passive"))
      (node (ref "C9") (pin "2") (pinfunction "2_2") (pintype "passive"))
      (node (ref "D2") (pin "A") (pinfunction "A_A") (pintype "passive"))
      (node (ref "J1") (pin "5") (pinfunction "5_5") (pintype "passive"))
      (node (ref "J1") (pin "S1") (pinfunction "S1_S1") (pintype "bidirectional"))
      (node (ref "J1") (pin "S2") (pinfunction "S1_S2") (pintype "bidirectional"))
      (node (ref "J1") (pin "S3") (pinfunction "S1_S3") (pintype "bidirectional"))
      (node (ref "J1") (pin "S4") (pinfunction "S1_S4") (pintype "bidirectional"))
      (node (ref "J1") (pin "S5") (pinfunction "S1_S5") (pintype "bidirectional"))
      (node (ref "J1") (pin "S6") (pinfunction "S1_S6") (pintype "bidirectional"))
      (node (ref "J2") (pin "1") (pinfunction "3_1") (pintype "passive"))
      (node (ref "J3") (pin "1") (pinfunction "3_1") (pintype "passive"))
      (node (ref "J4") (pin "1") (pinfunction "1_1") (pintype "passive"))
      (node (ref "J4") (pin "8") (pinfunction "8_8") (pintype "passive"))
      (node (ref "J4") (pin "9") (pinfunction "9_9") (pintype "passive"))
      (node (ref "J5") (pin "L4") (pinfunction "L4_L4") (pintype "passive"))
      (node (ref "J5") (pin "S1") (pinfunction "S1_S1") (pintype "power_in"))
      (node (ref "J5") (pin "S2") (pinfunction "S2_S2") (pintype "power_in"))
      (node (ref "R11") (pin "2") (pinfunction "2_2") (pintype "passive"))
      (node (ref "R12") (pin "2") (pinfunction "2_2") (pintype "passive"))
      (node (ref "R14") (pin "1") (pinfunction "1_1") (pintype "passive"))
      (node (ref "R16") (pin "2") (pinfunction "2_2") (pintype "passive"))
      (node (ref "R21") (pin "1") (pinfunction "1_1") (pintype "passive"))
      (node (ref "R23") (pin "1") (pinfunction "1_1") (pintype "passive"))
      (node (ref "R24") (pin "1") (pinfunction "1_1") (pintype "passive"))
      (node (ref "R28") (pin "1") (pinfunction "1_1") (pintype "passive"))
      (node (ref "R32") (pin "1") (pinfunction "1_1") (pintype "passive"))
      (node (ref "R6") (pin "2") (pinfunction "2_2") (pintype "passive"))
      (node (ref "S2") (pin "3") (pinfunction "S_3") (pintype "passive"))
      (node (ref "S2") (pin "4") (pinfunction "S1_4") (pintype "passive"))
      (node (ref "S3") (pin "3") (pinfunction "S_3") (pintype "passive"))
      (node (ref "S3") (pin "4") (pinfunction "S1_4") (pintype "passive"))
      (node (ref "U1") (pin "2") (pinfunction "GND_2") (pintype "power_in"))
      (node (ref "U2") (pin "1") (pinfunction "GND_1") (pintype "power_in"))
      (node (ref "U2") (pin "15") (pinfunction "GND_15") (pintype "power_in"))
      (node (ref "U2") (pin "38") (pinfunction "GND_38") (pintype "power_in"))
      (node (ref "U2") (pin "39") (pinfunction "GND_39") (pintype "power_in"))
      (node (ref "U3") (pin "8") (pinfunction "GND_8") (pintype "power_in"))
      (node (ref "U4") (pin "1") (pinfunction "GND_1") (pintype "bidirectional"))
      (node (ref "U5") (pin "2") (pinfunction "GND_2") (pintype "bidirectional"))
      (node (ref "U6") (pin "25") (pinfunction "VSS_25") (pintype "power_in"))
      (node (ref "U7") (pin "2") (pinfunction "GND_2") (pintype "power_in"))
      (node (ref "X2") (pin "2") (pinfunction "SH_2") (pintype "bidirectional"))
      (node (ref "X2") (pin "4") (pinfunction "SH_4") (pintype "bidirectional"))
    )
    (net (code "11") (name "HOST_RMII_CLK50") (class "Default")
      (node (ref "R5") (pin "2") (pinfunction "2_2") (pintype "passive"))
      (node (ref "U6") (pin "5") (pinfunction "XTAL1/CLKLN_5") (pintype "input"))
    )
    (net (code "12") (name "HOST_RMII_CRS_DV") (class "Default")
      (node (ref "R36") (pin "2") (pinfunction "2_2") (pintype "passive"))
      (node (ref "U2") (pin "12") (pinfunction "IO27_12") (pintype "bidirectional"))
    )
    (net (code "13") (name "HOST_RMII_MDC") (class "Default")
      (node (ref "U2") (pin "37") (pinfunction "IO23_37") (pintype "bidirectional"))
      (node (ref "U6") (pin "13") (pinfunction "MDC_13") (pintype "input"))
    )
    (net (code "14") (name "HOST_RMII_MDIO") (class "Default")
      (node (ref "R33") (pin "1") (pinfunction "1_1") (pintype "passive"))
      (node (ref "U2") (pin "30") (pinfunction "IO18_30") (pintype "bidirectional"))
      (node (ref "U6") (pin "12") (pinfunction "MDIO_12") (pintype "bidirectional"))
    )
    (net (code "15") (name "HOST_RMII_RXD0") (class "Default")
      (node (ref "R34") (pin "2") (pinfunction "2_2") (pintype "passive"))
      (node (ref "U2") (pin "10") (pinfunction "IO25_10") (pintype "bidirectional"))
    )
    (net (code "16") (name "HOST_RMII_RXD1") (class "Default")
      (node (ref "R35") (pin "2") (pinfunction "2_2") (pintype "passive"))
      (node (ref "U2") (pin "11") (pinfunction "IO26_11") (pintype "bidirectional"))
    )
    (net (code "17") (name "HOST_RMII_TXD0") (class "Default")
      (node (ref "U2") (pin "31") (pinfunction "IO19_31") (pintype "bidirectional"))
      (node (ref "U6") (pin "17") (pinfunction "TXD0_17") (pintype "input"))
    )
    (net (code "18") (name "HOST_RMII_TXD1") (class "Default")
      (node (ref "U2") (pin "36") (pinfunction "IO22_36") (pintype "bidirectional"))
      (node (ref "U6") (pin "18") (pinfunction "TXD1_18") (pintype "input"))
    )
    (net (code "19") (name "HOST_RMII_TX_EN") (class "Default")
      (node (ref "U2") (pin "33") (pinfunction "IO21_33") (pintype "bidirectional"))
      (node (ref "U6") (pin "16") (pinfunction "TXEN_16") (pintype "input"))
    )
    (net (code "20") (name "IO0_BOOTMODE_SW2_UP") (class "Default")
      (node (ref "C17") (pin "1") (pinfunction "1_1") (pintype "passive"))
      (node (ref "Q1") (pin "3") (pinfunction "C_3") (pintype "passive"))
      (node (ref "R22") (pin "1") (pinfunction "1_1") (pintype "passive"))
      (node (ref "S2") (pin "1") (pinfunction "P_1") (pintype "passive"))
      (node (ref "S2") (pin "2") (pinfunction "P1_2") (pintype "passive"))
      (node (ref "U2") (pin "25") (pinfunction "IO0_25") (pintype "bidirectional"))
    )
    (net (code "21") (name "IO2_5VIO_1A_DOWN") (class "Default")
      (node (ref "R23") (pin "2") (pinfunction "2_2") (pintype "passive"))
      (node (ref "R26") (pin "1") (pinfunction "1_1") (pintype "passive"))
      (node (ref "U2") (pin "24") (pinfunction "IO2_24") (pintype "bidirectional"))
      (node (ref "U7") (pin "3") (pinfunction "A_3") (pintype "input"))
    )
    (net (code "22") (name "IO4_RIGHT_EYE") (class "Default")
      (node (ref "R46") (pin "2") (pinfunction "2_2") (pintype "passive"))
      (node (ref "U2") (pin "26") (pinfunction "IO4_26") (pintype "bidirectional"))
    )
    (net (code "23") (name "IO5_3V3IO_2_UP") (class "Default")
      (node (ref "J4") (pin "3") (pinfunction "3_3") (pintype "passive"))
      (node (ref "R9") (pin "2") (pinfunction "2_2") (pintype "passive"))
      (node (ref "U2") (pin "29") (pinfunction "IO5_29") (pintype "bidirectional"))
    )
    (net (code "24") (name "IO12_3V3IO_3_DOWN") (class "Default")
      (node (ref "J4") (pin "2") (pinfunction "2_2") (pintype "passive"))
      (node (ref "R11") (pin "1") (pinfunction "1_1") (pintype "passive"))
      (node (ref "U2") (pin "14") (pinfunction "IO12_14") (pintype "bidirectional"))
    )
    (net (code "25") (name "IO13_LED0R") (class "Default")
      (node (ref "R19") (pin "1") (pinfunction "1_1") (pintype "passive"))
      (node (ref "U2") (pin "16") (pinfunction "IO13_16") (pintype "bidirectional"))
    )
    (net (code "26") (name "IO14_LED0B") (class "Default")
      (node (ref "R17") (pin "1") (pinfunction "1_1") (pintype "passive"))
      (node (ref "U2") (pin "13") (pinfunction "IO14_13") (pintype "bidirectional"))
    )
    (net (code "27") (name "IO15_ETH_RST_UP") (class "Default")
      (node (ref "R10") (pin "2") (pinfunction "2_2") (pintype "passive"))
      (node (ref "R25") (pin "1") (pinfunction "1_1") (pintype "passive"))
      (node (ref "U2") (pin "23") (pinfunction "IO15_23") (pintype "bidirectional"))
    )
    (net (code "28") (name "IO16_LEFT_EYE") (class "Default")
      (node (ref "R45") (pin "2") (pinfunction "2_2") (pintype "passive"))
      (node (ref "U2") (pin "27") (pinfunction "IO16_27") (pintype "bidirectional"))
    )
    (net (code "29") (name "IO32_5VIO_0A") (class "Default")
      (node (ref "R2") (pin "1") (pinfunction "1_1") (pintype "passive"))
      (node (ref "U1") (pin "3") (pinfunction "A_3") (pintype "input"))
      (node (ref "U2") (pin "8") (pinfunction "IO32_8") (pintype "bidirectional"))
    )
    (net (code "30") (name "IO33_LED0G") (class "Default")
      (node (ref "R18") (pin "1") (pinfunction "1_1") (pintype "passive"))
      (node (ref "U2") (pin "9") (pinfunction "IO33_9") (pintype "bidirectional"))
    )
    (net (code "31") (name "IO34_SW1") (class "Default")
      (node (ref "C13") (pin "2") (pinfunction "2_2") (pintype "passive"))
      (node (ref "R16") (pin "1") (pinfunction "1_1") (pintype "passive"))
      (node (ref "S1") (pin "1") (pinfunction "P_1") (pintype "passive"))
      (node (ref "S1") (pin "2") (pinfunction "P1_2") (pintype "passive"))
      (node (ref "U2") (pin "6") (pinfunction "IO34_6") (pintype "bidirectional"))
    )
    (net (code "32") (name "IO36_VSENSE") (class "Default")
      (node (ref "C8") (pin "1") (pinfunction "1_1") (pintype "passive"))
      (node (ref "R13") (pin "1") (pinfunction "1_1") (pintype "passive"))
      (node (ref "R14") (pin "2") (pinfunction "2_2") (pintype "passive"))
      (node (ref "U2") (pin "4") (pinfunction "SENSOR_VP_4") (pintype "input"))
    )
    (net (code "33") (name "IO39_3V3IO_1_DOWN") (class "Default")
      (node (ref "J4") (pin "4") (pinfunction "4_4") (pintype "passive"))
      (node (ref "R12") (pin "1") (pinfunction "1_1") (pintype "passive"))
      (node (ref "U2") (pin "5") (pinfunction "SENSOR_VN_5") (pintype "input"))
    )
    (net (code "34") (name "Net-(C16-Pad1)") (class "Default")
      (node (ref "C16") (pin "1") (pinfunction "1_1") (pintype "passive"))
      (node (ref "C32") (pin "1") (pinfunction "1_1") (pintype "passive"))
      (node (ref "J7") (pin "2") (pinfunction "2_2") (pintype "passive"))
      (node (ref "L1") (pin "2") (pinfunction "2_2") (pintype "passive"))
      (node (ref "R20") (pin "2") (pinfunction "2_2") (pintype "passive"))
      (node (ref "R44") (pin "1") (pinfunction "1_1") (pintype "passive"))
    )
    (net (code "35") (name "Net-(D3-B)") (class "Default")
      (node (ref "D3") (pin "4") (pinfunction "B_4") (pintype "passive"))
      (node (ref "R17") (pin "2") (pinfunction "2_2") (pintype "passive"))
    )
    (net (code "36") (name "Net-(D3-G)") (class "Default")
      (node (ref "D3") (pin "3") (pinfunction "G_3") (pintype "passive"))
      (node (ref "R18") (pin "2") (pinfunction "2_2") (pintype "passive"))
    )
    (net (code "37") (name "Net-(D3-R)") (class "Default")
      (node (ref "D3") (pin "1") (pinfunction "R_1") (pintype "passive"))
      (node (ref "R19") (pin "2") (pinfunction "2_2") (pintype "passive"))
    )
    (net (code "38") (name "Net-(D5-PadC)") (class "Default")
      (node (ref "D5") (pin "C") (pinfunction "C_C") (pintype "passive"))
      (node (ref "R45") (pin "1") (pinfunction "1_1") (pintype "passive"))
    )
    (net (code "39") (name "Net-(D6-PadC)") (class "Default")
      (node (ref "D6") (pin "C") (pinfunction "C_C") (pintype "passive"))
      (node (ref "R46") (pin "1") (pinfunction "1_1") (pintype "passive"))
    )
    (net (code "40") (name "Net-(D7-PadC)") (class "Default")
      (node (ref "D7") (pin "C") (pinfunction "C_C") (pintype "passive"))
      (node (ref "R24") (pin "2") (pinfunction "2_2") (pintype "passive"))
    )
    (net (code "41") (name "Net-(J5-PadL2)") (class "Default")
      (node (ref "J5") (pin "L2") (pinfunction "L2_L2") (pintype "passive"))
      (node (ref "R40") (pin "2") (pinfunction "2_2") (pintype "passive"))
    )
    (net (code "42") (name "Net-(J5-PadL3)") (class "Default")
      (node (ref "J5") (pin "L3") (pinfunction "L3_L3") (pintype "passive"))
      (node (ref "R41") (pin "2") (pinfunction "2_2") (pintype "passive"))
    )
    (net (code "43") (name "Net-(Q1-B)") (class "Default")
      (node (ref "Q1") (pin "1") (pinfunction "B_1") (pintype "passive"))
      (node (ref "R7") (pin "2") (pinfunction "2_2") (pintype "passive"))
    )
    (net (code "44") (name "Net-(Q2-B)") (class "Default")
      (node (ref "Q2") (pin "1") (pinfunction "B_1") (pintype "passive"))
      (node (ref "R8") (pin "2") (pinfunction "2_2") (pintype "passive"))
    )
    (net (code "45") (name "Net-(U2-IO17)") (class "Default")
      (node (ref "R5") (pin "1") (pinfunction "1_1") (pintype "passive"))
      (node (ref "U2") (pin "28") (pinfunction "IO17_28") (pintype "bidirectional"))
    )
    (net (code "46") (name "Net-(U3-NOS#)") (class "Default")
      (node (ref "R6") (pin "1") (pinfunction "1_1") (pintype "passive"))
      (node (ref "U3") (pin "20") (pinfunction "NOS#_20") (pintype "power_in"))
    )
    (net (code "47") (name "Net-(U3-RXD)") (class "Default")
      (node (ref "R47") (pin "2") (pinfunction "2_2") (pintype "passive"))
      (node (ref "U3") (pin "4") (pinfunction "RXD_4") (pintype "input"))
    )
    (net (code "48") (name "Net-(U3-TXD)") (class "Default")
      (node (ref "R3") (pin "2") (pinfunction "2_2") (pintype "passive"))
      (node (ref "U3") (pin "3") (pinfunction "TXD_3") (pintype "output"))
    )
    (net (code "49") (name "Net-(U3-XI)") (class "Default")
      (node (ref "C31") (pin "1") (pinfunction "1_1") (pintype "passive"))
      (node (ref "U3") (pin "9") (pinfunction "XI_9") (pintype "input"))
      (node (ref "X2") (pin "3") (pinfunction "2_3") (pintype "bidirectional"))
    )
    (net (code "50") (name "Net-(U3-XO)") (class "Default")
      (node (ref "C30") (pin "1") (pinfunction "1_1") (pintype "passive"))
      (node (ref "U3") (pin "10") (pinfunction "XO_10") (pintype "output"))
      (node (ref "X2") (pin "1") (pinfunction "1_1") (pintype "bidirectional"))
    )
    (net (code "51") (name "Net-(U5-BST)") (class "Default")
      (node (ref "C15") (pin "1") (pinfunction "1_1") (pintype "passive"))
      (node (ref "U5") (pin "1") (pinfunction "BST_1") (pintype "bidirectional"))
    )
    (net (code "52") (name "Net-(U5-EN)") (class "Default")
      (node (ref "R15") (pin "2") (pinfunction "2_2") (pintype "passive"))
      (node (ref "U5") (pin "4") (pinfunction "EN_4") (pintype "bidirectional"))
    )
    (net (code "53") (name "Net-(U5-FB)") (class "Default")
      (node (ref "R20") (pin "1") (pinfunction "1_1") (pintype "passive"))
      (node (ref "R21") (pin "2") (pinfunction "2_2") (pintype "passive"))
      (node (ref "U5") (pin "3") (pinfunction "FB_3") (pintype "bidirectional"))
    )
    (net (code "54") (name "Net-(U5-LX)") (class "Default")
      (node (ref "C15") (pin "2") (pinfunction "2_2") (pintype "passive"))
      (node (ref "D2") (pin "C") (pinfunction "C_C") (pintype "passive"))
      (node (ref "L1") (pin "1") (pinfunction "1_1") (pintype "passive"))
      (node (ref "U5") (pin "6") (pinfunction "LX_6") (pintype "bidirectional"))
    )
    (net (code "55") (name "Net-(U5-VIN)") (class "Default")
      (node (ref "R15") (pin "1") (pinfunction "1_1") (pintype "passive"))
      (node (ref "R43") (pin "2") (pinfunction "2_2") (pintype "passive"))
      (node (ref "U5") (pin "5") (pinfunction "VIN_5") (pintype "bidirectional"))
    )
    (net (code "56") (name "Net-(U6-CRS_DV{slash}MODE2)") (class "Default")
      (node (ref "R31") (pin "1") (pinfunction "1_1") (pintype "passive"))
      (node (ref "R36") (pin "1") (pinfunction "1_1") (pintype "passive"))
      (node (ref "U6") (pin "11") (pinfunction "CRS_DV/MODE2_11") (pintype "bidirectional"))
    )
    (net (code "57") (name "Net-(U6-LED1{slash}REGOFF)") (class "Default")
      (node (ref "R41") (pin "1") (pinfunction "1_1") (pintype "passive"))
      (node (ref "U6") (pin "3") (pinfunction "LED1/REGOFF_3") (pintype "bidirectional"))
    )
    (net (code "58") (name "Net-(U6-LED2{slash}~{NINTSEL})") (class "Default")
      (node (ref "R40") (pin "1") (pinfunction "1_1") (pintype "passive"))
      (node (ref "U6") (pin "2") (pinfunction "LED2/~{NINTSEL}_2") (pintype "bidirectional"))
    )
    (net (code "59") (name "Net-(U6-RBIAS)") (class "Default")
      (node (ref "R28") (pin "2") (pinfunction "2_2") (pintype "passive"))
      (node (ref "U6") (pin "24") (pinfunction "RBIAS_24") (pintype "input"))
    )
    (net (code "60") (name "Net-(U6-RXD0{slash}MODE0)") (class "Default")
      (node (ref "R29") (pin "1") (pinfunction "1_1") (pintype "passive"))
      (node (ref "R34") (pin "1") (pinfunction "1_1") (pintype "passive"))
      (node (ref "U6") (pin "8") (pinfunction "RXD0/MODE0_8") (pintype "bidirectional"))
    )
    (net (code "61") (name "Net-(U6-RXD1{slash}MODE1)") (class "Default")
      (node (ref "R30") (pin "1") (pinfunction "1_1") (pintype "passive"))
      (node (ref "R35") (pin "1") (pinfunction "1_1") (pintype "passive"))
      (node (ref "U6") (pin "7") (pinfunction "RXD1/MODE1_7") (pintype "bidirectional"))
    )
    (net (code "62") (name "Net-(U6-RXER{slash}PHYADO)") (class "Default")
      (node (ref "R32") (pin "2") (pinfunction "2_2") (pintype "passive"))
      (node (ref "U6") (pin "10") (pinfunction "RXER/PHYADO_10") (pintype "bidirectional"))
    )
    (net (code "63") (name "PHY_VDDCR") (class "Default")
      (node (ref "C22") (pin "1") (pinfunction "1_1") (pintype "passive"))
      (node (ref "C24") (pin "1") (pinfunction "1_1") (pintype "passive"))
      (node (ref "C25") (pin "1") (pinfunction "1_1") (pintype "passive"))
      (node (ref "U6") (pin "6") (pinfunction "VDDCR_6") (pintype "power_in"))
    )
    (net (code "64") (name "RD_N") (class "Default")
      (node (ref "J5") (pin "R8") (pinfunction "RD-_R8") (pintype "input"))
      (node (ref "R37") (pin "1") (pinfunction "1_1") (pintype "passive"))
      (node (ref "U6") (pin "22") (pinfunction "RXN_22") (pintype "bidirectional"))
    )
    (net (code "65") (name "RD_P") (class "Default")
      (node (ref "J5") (pin "R7") (pinfunction "RD+_R7") (pintype "input"))
      (node (ref "R38") (pin "1") (pinfunction "1_1") (pintype "passive"))
      (node (ref "U6") (pin "23") (pinfunction "RXP_23") (pintype "bidirectional"))
    )
    (net (code "66") (name "TD_N") (class "Default")
      (node (ref "J5") (pin "R2") (pinfunction "TD-_R2") (pintype "input"))
      (node (ref "R39") (pin "1") (pinfunction "1_1") (pintype "passive"))
      (node (ref "U6") (pin "20") (pinfunction "TXN_20") (pintype "bidirectional"))
    )
    (net (code "67") (name "TD_P") (class "Default")
      (node (ref "J5") (pin "R1") (pinfunction "TD+_R1") (pintype "input"))
      (node (ref "R42") (pin "1") (pinfunction "1_1") (pintype "passive"))
      (node (ref "U6") (pin "21") (pinfunction "TXP_21") (pintype "bidirectional"))
    )
    (net (code "68") (name "UART_DTR") (class "Default")
      (node (ref "Q1") (pin "2") (pinfunction "E_2") (pintype "passive"))
      (node (ref "R8") (pin "1") (pinfunction "1_1") (pintype "passive"))
      (node (ref "U3") (pin "15") (pinfunction "DTR#_15") (pintype "output"))
    )
    (net (code "69") (name "UART_RTS") (class "Default")
      (node (ref "Q2") (pin "2") (pinfunction "E_2") (pintype "passive"))
      (node (ref "R7") (pin "1") (pinfunction "1_1") (pintype "passive"))
      (node (ref "U3") (pin "16") (pinfunction "RTS#_16") (pintype "output"))
    )
    (net (code "70") (name "UART_RXD") (class "Default")
      (node (ref "R3") (pin "1") (pinfunction "1_1") (pintype "passive"))
      (node (ref "U2") (pin "34") (pinfunction "RXD0_34") (pintype "bidirectional"))
    )
    (net (code "71") (name "UART_TXD") (class "Default")
      (node (ref "R47") (pin "1") (pinfunction "1_1") (pintype "passive"))
      (node (ref "U2") (pin "35") (pinfunction "TXD0_35") (pintype "bidirectional"))
    )
    (net (code "72") (name "USBD_N") (class "Default")
      (node (ref "J1") (pin "2") (pinfunction "2_2") (pintype "passive"))
      (node (ref "U3") (pin "7") (pinfunction "UD-_7") (pintype "bidirectional"))
    )
    (net (code "73") (name "USBD_P") (class "Default")
      (node (ref "J1") (pin "3") (pinfunction "3_3") (pintype "passive"))
      (node (ref "U3") (pin "6") (pinfunction "UD+_6") (pintype "bidirectional"))
    )
    (net (code "74") (name "VBUS") (class "Default")
      (node (ref "C3") (pin "1") (pinfunction "1_1") (pintype "passive"))
      (node (ref "J1") (pin "1") (pinfunction "1_1") (pintype "passive"))
      (node (ref "R4") (pin "1") (pinfunction "1_1") (pintype "passive"))
    )
    (net (code "75") (name "VDDA") (class "Default")
      (node (ref "C26") (pin "1") (pinfunction "1_1") (pintype "passive"))
      (node (ref "C27") (pin "1") (pinfunction "1_1") (pintype "passive"))
      (node (ref "C28") (pin "1") (pinfunction "1_1") (pintype "passive"))
      (node (ref "C29") (pin "1") (pinfunction "1_1") (pintype "passive"))
      (node (ref "J5") (pin "L1") (pinfunction "L1_L1") (pintype "passive"))
      (node (ref "J5") (pin "R3") (pinfunction "CT_R3") (pintype "input"))
      (node (ref "L2") (pin "2") (pinfunction "2_2") (pintype "passive"))
      (node (ref "R37") (pin "2") (pinfunction "2_2") (pintype "passive"))
      (node (ref "R38") (pin "2") (pinfunction "2_2") (pintype "passive"))
      (node (ref "R39") (pin "2") (pinfunction "2_2") (pintype "passive"))
      (node (ref "R42") (pin "2") (pinfunction "2_2") (pintype "passive"))
      (node (ref "U6") (pin "1") (pinfunction "VDD2A_1") (pintype "power_in"))
      (node (ref "U6") (pin "19") (pinfunction "VDD1A_19") (pintype "power_in"))
    )
    (net (code "76") (name "VLED") (class "Default")
      (node (ref "C11") (pin "1") (pinfunction "1_1") (pintype "passive"))
      (node (ref "C12") (pin "1") (pinfunction "1_1") (pintype "passive"))
      (node (ref "C18") (pin "1") (pinfunction "1_1") (pintype "passive"))
      (node (ref "C19") (pin "1") (pinfunction "1_1") (pintype "passive"))
      (node (ref "J2") (pin "3") (pinfunction "1_3") (pintype "passive"))
      (node (ref "J3") (pin "3") (pinfunction "1_3") (pintype "passive"))
      (node (ref "R13") (pin "2") (pinfunction "2_2") (pintype "passive"))
      (node (ref "R4") (pin "2") (pinfunction "2_2") (pintype "passive"))
      (node (ref "R43") (pin "1") (pinfunction "1_1") (pintype "passive"))
      (node (ref "U4") (pin "3") (pinfunction "VIN_3") (pintype "bidirectional"))
    )
    (net (code "77") (name "unconnected-(J1-Pad4)") (class "Default")
      (node (ref "J1") (pin "4") (pinfunction "4_4") (pintype "passive"))
    )
    (net (code "78") (name "unconnected-(J5-PadR4)") (class "Default")
      (node (ref "J5") (pin "R4") (pinfunction "R4_R4") (pintype "input"))
    )
    (net (code "79") (name "unconnected-(J5-PadR5)") (class "Default")
      (node (ref "J5") (pin "R5") (pinfunction "R5_R5") (pintype "input"))
    )
    (net (code "80") (name "unconnected-(J5-PadR6)") (class "Default")
      (node (ref "J5") (pin "R6") (pinfunction "R6_R6") (pintype "input"))
    )
    (net (code "81") (name "unconnected-(U2-IO35-Pad7)") (class "Default")
      (node (ref "U2") (pin "7") (pinfunction "IO35_7") (pintype "bidirectional"))
    )
    (net (code "82") (name "unconnected-(U2-SCL{slash}CLK-Pad20)") (class "Default")
      (node (ref "U2") (pin "20") (pinfunction "SCL/CLK_20") (pintype "bidirectional"))
    )
    (net (code "83") (name "unconnected-(U2-SCS{slash}CMD-Pad19)") (class "Default")
      (node (ref "U2") (pin "19") (pinfunction "SCS/CMD_19") (pintype "bidirectional"))
    )
    (net (code "84") (name "unconnected-(U2-SDI{slash}SD1-Pad22)") (class "Default")
      (node (ref "U2") (pin "22") (pinfunction "SDI/SD1_22") (pintype "bidirectional"))
    )
    (net (code "85") (name "unconnected-(U2-SDO{slash}SD0-Pad21)") (class "Default")
      (node (ref "U2") (pin "21") (pinfunction "SDO/SD0_21") (pintype "bidirectional"))
    )
    (net (code "86") (name "unconnected-(U2-SHD{slash}SD2-Pad17)") (class "Default")
      (node (ref "U2") (pin "17") (pinfunction "SHD/SD2_17") (pintype "bidirectional"))
    )
    (net (code "87") (name "unconnected-(U2-SWP{slash}SD3-Pad18)") (class "Default")
      (node (ref "U2") (pin "18") (pinfunction "SWP/SD3_18") (pintype "bidirectional"))
    )
    (net (code "88") (name "unconnected-(U3-ACT#-Pad2)") (class "Default")
      (node (ref "U3") (pin "2") (pinfunction "ACT#_2") (pintype "output"))
    )
    (net (code "89") (name "unconnected-(U3-CKO-Pad1)") (class "Default")
      (node (ref "U3") (pin "1") (pinfunction "CKO_1") (pintype "output"))
    )
    (net (code "90") (name "unconnected-(U3-CTS#-Pad11)") (class "Default")
      (node (ref "U3") (pin "11") (pinfunction "CTS#_11") (pintype "input"))
    )
    (net (code "91") (name "unconnected-(U3-DCD#-Pad14)") (class "Default")
      (node (ref "U3") (pin "14") (pinfunction "DCD#_14") (pintype "input"))
    )
    (net (code "92") (name "unconnected-(U3-DSR#-Pad12)") (class "Default")
      (node (ref "U3") (pin "12") (pinfunction "DSR#_12") (pintype "input"))
    )
    (net (code "93") (name "unconnected-(U3-NC-Pad17)") (class "Default")
      (node (ref "U3") (pin "17") (pinfunction "NC_17") (pintype "no_connect"))
    )
    (net (code "94") (name "unconnected-(U3-R232-Pad18)") (class "Default")
      (node (ref "U3") (pin "18") (pinfunction "R232_18") (pintype "input"))
    )
    (net (code "95") (name "unconnected-(U3-RI#-Pad13)") (class "Default")
      (node (ref "U3") (pin "13") (pinfunction "RI#_13") (pintype "input"))
    )
    (net (code "96") (name "unconnected-(U6-XTAL2-Pad4)") (class "Default")
      (node (ref "U6") (pin "4") (pinfunction "XTAL2_4") (pintype "output"))
    )
    (net (code "97") (name "unconnected-(U6-~{NINT}{slash}REFCLKO-Pad14)") (class "Default")
      (node (ref "U6") (pin "14") (pinfunction "~{NINT}/REFCLKO_14") (pintype "output"))
    )
    (net (code "98") (name "~{RESET}") (class "Default")
      (node (ref "C2") (pin "1") (pinfunction "1_1") (pintype "passive"))
      (node (ref "Q2") (pin "3") (pinfunction "C_3") (pintype "passive"))
      (node (ref "R1") (pin "1") (pinfunction "1_1") (pintype "passive"))
      (node (ref "S3") (pin "1") (pinfunction "P_1") (pintype "passive"))
      (node (ref "S3") (pin "2") (pinfunction "P1_2") (pintype "passive"))
      (node (ref "U2") (pin "3") (pinfunction "EN_3") (pintype "input"))
    )
  )
)
